# ftdi_eeprom.net
KiCad netlist of a schematic drawn in Altium Designer
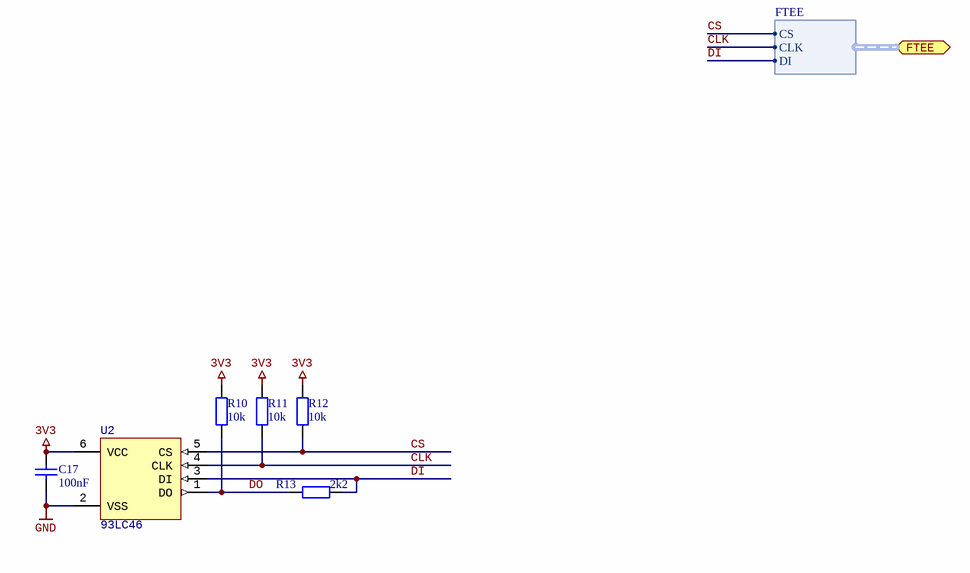
[diagram p0: ftdi_eeprom.SchDoc]

(export (version "E")
  (design (tool "Eeschema 10.0.6"))
  (components
    (comp (ref "C17")
      (value "100nF")
      (footprint "CAPC1608N")
      (description "Capacitor")
      (libsource (lib "Discrete") (part "Capacitor"))
    )
    (comp (ref "R10")
      (value "10k")
      (footprint "RESC1608N")
      (description "Resistor")
      (fields (field (name "TOLERANCE") "1%") (field (name "POWER") "0W"))
      (libsource (lib "Discrete") (part "Resistor"))
    )
    (comp (ref "R11")
      (value "10k")
      (footprint "RESC1608N")
      (description "Resistor")
      (fields (field (name "TOLERANCE") "1%") (field (name "POWER") "0W"))
      (libsource (lib "Discrete") (part "Resistor"))
    )
    (comp (ref "R12")
      (value "10k")
      (footprint "RESC1608N")
      (description "Resistor")
      (fields (field (name "TOLERANCE") "1%") (field (name "POWER") "0W"))
      (libsource (lib "Discrete") (part "Resistor"))
    )
    (comp (ref "R13")
      (value "2k2")
      (footprint "RESC1608N")
      (description "Resistor")
      (fields (field (name "TOLERANCE") "1%") (field (name "POWER") "0W"))
      (libsource (lib "") (part "Resistor_1"))
    )
    (comp (ref "U2")
      (value "93LC46")
      (footprint "SOT23-6")
      (description "1K Microwire Compatible Serial EEPROM")
      (libsource (lib "my_various_devices") (part "93LC46"))
    )
  )
  (nets
    (net (code "2") (name "/CLK") (class "Default")
      (node (ref "R11") (pin "2") (pinfunction "2_2") (pintype "passive"))
      (node (ref "U2") (pin "4") (pinfunction "CLK_4") (pintype "input"))
    )
    (net (code "3") (name "/CS") (class "Default")
      (node (ref "R12") (pin "2") (pinfunction "2_2") (pintype "passive"))
      (node (ref "U2") (pin "5") (pinfunction "CS_5") (pintype "input"))
    )
    (net (code "4") (name "/DI") (class "Default")
      (node (ref "R13") (pin "2") (pinfunction "2_2") (pintype "passive"))
      (node (ref "U2") (pin "3") (pinfunction "DI_3") (pintype "input"))
    )
    (net (code "5") (name "/DO") (class "Default")
      (node (ref "R10") (pin "2") (pinfunction "2_2") (pintype "passive"))
      (node (ref "R13") (pin "1") (pinfunction "1_1") (pintype "passive"))
      (node (ref "U2") (pin "1") (pinfunction "DO_1") (pintype "output"))
    )
    (net (code "7") (name "3V3") (class "Default")
      (node (ref "C17") (pin "2") (pinfunction "2_2") (pintype "passive"))
      (node (ref "R10") (pin "1") (pinfunction "1_1") (pintype "passive"))
      (node (ref "R11") (pin "1") (pinfunction "1_1") (pintype "passive"))
      (node (ref "R12") (pin "1") (pinfunction "1_1") (pintype "passive"))
      (node (ref "U2") (pin "6") (pinfunction "VCC_6") (pintype "power_in"))
    )
    (net (code "8") (name "GND") (class "Default")
      (node (ref "C17") (pin "1") (pinfunction "1_1") (pintype "passive"))
      (node (ref "U2") (pin "2") (pinfunction "VSS_2") (pintype "power_in"))
    )
  )
)
